# ch340_usbc.net
KiCad netlist of a schematic drawn in Altium Designer
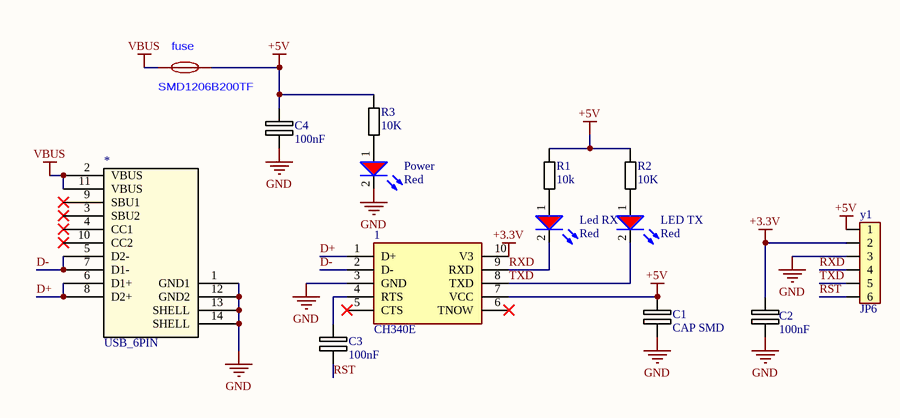
[diagram p0: ch340_usbc.SchDoc]

(export (version "E")
  (design (tool "Eeschema 10.0.6"))
  (components
    (comp (ref "*")
      (value "USB_6PIN")
      (footprint "USB-C-SMD_TYPE-C-6PIN-2MD-073")
      (libsource (lib "iot_vision") (part "USB_6PIN"))
    )
    (comp (ref "1") (value "CH340E") (footprint "ADS1115 SMD") (libsource (lib "TEST") (part "CH340E")))
    (comp (ref "C1")
      (value "CAP SMD")
      (footprint "C-0805")
      (description "Capacitor Polarised")
      (fields
        (field (name "MANUFACTURER_PART_NUMBER") "TAJC227K006RNJV")
        (field (name "MOUSER PART NUMBER") "581-TAJC227K006RNJV")
      )
      (libsource (lib "TEST") (part "CAP SMD"))
    )
    (comp (ref "C2")
      (value "100nF")
      (footprint "C-0805")
      (description "Capacitor Polarised")
      (fields
        (field (name "MANUFACTURER_PART_NUMBER") "TAJC227K006RNJV")
        (field (name "MOUSER PART NUMBER") "581-TAJC227K006RNJV")
      )
      (libsource (lib "") (part "CAP SMD_1"))
    )
    (comp (ref "C3")
      (value "100nF")
      (footprint "C-0805")
      (description "Capacitor Polarised")
      (fields
        (field (name "MANUFACTURER_PART_NUMBER") "TAJC227K006RNJV")
        (field (name "MOUSER PART NUMBER") "581-TAJC227K006RNJV")
      )
      (libsource (lib "TEST") (part "CAP SMD"))
    )
    (comp (ref "C4")
      (value "100nF")
      (footprint "C-0805")
      (description "Capacitor Polarised")
      (fields
        (field (name "MANUFACTURER_PART_NUMBER") "TAJC227K006RNJV")
        (field (name "MOUSER PART NUMBER") "581-TAJC227K006RNJV")
      )
      (libsource (lib "TEST") (part "CAP SMD"))
    )
    (comp (ref "fuse")
      (value "SMD1206B200TF")
      (footprint "F1206")
      (libsource (lib "Free Documents") (part "SMD1206B200TF"))
    )
    (comp (ref "Led RX")
      (value "Red")
      (footprint "Led 0805R")
      (description "LED Red 2mA 1.8V 0805")
      (fields (field (name "Comment") "LED-0805RVC"))
      (libsource (lib "TEST") (part "LED-0805RVC"))
    )
    (comp (ref "LED TX")
      (value "Red")
      (footprint "Led 0805R")
      (description "LED Red 2mA 1.8V 0805")
      (fields (field (name "Comment") "LED-0805RVC"))
      (libsource (lib "TEST") (part "LED-0805RVC"))
    )
    (comp (ref "Power")
      (value "LED-0805RVC")
      (footprint "Led 0805R")
      (description "LED Red 2mA 1.8V 0805")
      (fields (field (name "ALTIUM_UNNAMED_1") "Red"))
      (libsource (lib "TEST") (part "LED-0805RVC"))
    )
    (comp (ref "R1") (value "10k") (footprint "R0603") (libsource (lib "iot_vision") (part "res_0603")))
    (comp (ref "R2")
      (value "10K")
      (footprint "R0603")
      (description "Resistor")
      (libsource (lib "SamacSys") (part "Resistor"))
    )
    (comp (ref "R3")
      (value "10K")
      (footprint "R0603")
      (description "Resistor")
      (libsource (lib "SamacSys") (part "Resistor"))
    )
    (comp (ref "y1") (value "JP6") (footprint "JP6-D1T") (libsource (lib "TEST") (part "JP6")))
  )
  (nets
    (net (code "1") (name "+3.3V") (class "Default")
      (node (ref "1") (pin "10") (pinfunction "V3_10") (pintype "passive"))
      (node (ref "C2") (pin "1") (pinfunction "+_1") (pintype "passive"))
      (node (ref "y1") (pin "2") (pinfunction "2_2") (pintype "passive"))
    )
    (net (code "2") (name "+5V") (class "Default")
      (node (ref "1") (pin "7") (pinfunction "VCC_7") (pintype "passive"))
      (node (ref "C1") (pin "2") (pinfunction "-_2") (pintype "passive"))
      (node (ref "C4") (pin "2") (pinfunction "-_2") (pintype "passive"))
      (node (ref "R1") (pin "2") (pinfunction "2_2") (pintype "passive"))
      (node (ref "R2") (pin "2") (pinfunction "2_2") (pintype "passive"))
      (node (ref "R3") (pin "2") (pinfunction "2_2") (pintype "passive"))
      (node (ref "fuse") (pin "2") (pinfunction "2_2") (pintype "passive"))
      (node (ref "y1") (pin "1") (pinfunction "1_1") (pintype "passive"))
    )
    (net (code "3") (name "/D+") (class "Default")
      (node (ref "*") (pin "6") (pinfunction "D1+_6") (pintype "passive"))
      (node (ref "*") (pin "8") (pinfunction "D2+_8") (pintype "passive"))
      (node (ref "1") (pin "1") (pinfunction "D+_1") (pintype "passive"))
    )
    (net (code "4") (name "/D-") (class "Default")
      (node (ref "*") (pin "5") (pinfunction "D2-_5") (pintype "passive"))
      (node (ref "*") (pin "7") (pinfunction "D1-_7") (pintype "passive"))
      (node (ref "1") (pin "2") (pinfunction "D-_2") (pintype "passive"))
    )
    (net (code "5") (name "/RST") (class "Default")
      (node (ref "C3") (pin "1") (pinfunction "+_1") (pintype "passive"))
      (node (ref "y1") (pin "6") (pinfunction "6_6") (pintype "passive"))
    )
    (net (code "6") (name "/RXD") (class "Default")
      (node (ref "1") (pin "9") (pinfunction "RXD_9") (pintype "passive"))
      (node (ref "Led RX") (pin "2") (pinfunction "K_2") (pintype "passive"))
      (node (ref "y1") (pin "4") (pinfunction "4_4") (pintype "passive"))
    )
    (net (code "7") (name "/TXD") (class "Default")
      (node (ref "1") (pin "8") (pinfunction "TXD_8") (pintype "passive"))
      (node (ref "LED TX") (pin "2") (pinfunction "K_2") (pintype "passive"))
      (node (ref "y1") (pin "5") (pinfunction "5_5") (pintype "passive"))
    )
    (net (code "8") (name "GND") (class "Default")
      (node (ref "*") (pin "1") (pinfunction "GND1_1") (pintype "passive"))
      (node (ref "*") (pin "12") (pinfunction "GND2_12") (pintype "passive"))
      (node (ref "*") (pin "13") (pinfunction "SHELL_13") (pintype "passive"))
      (node (ref "*") (pin "14") (pinfunction "SHELL_14") (pintype "passive"))
      (node (ref "1") (pin "3") (pinfunction "GND_3") (pintype "passive"))
      (node (ref "C1") (pin "1") (pinfunction "+_1") (pintype "passive"))
      (node (ref "C2") (pin "2") (pinfunction "-_2") (pintype "passive"))
      (node (ref "C4") (pin "1") (pinfunction "+_1") (pintype "passive"))
      (node (ref "Power") (pin "2") (pinfunction "K_2") (pintype "passive"))
      (node (ref "y1") (pin "3") (pinfunction "3_3") (pintype "passive"))
    )
    (net (code "9") (name "Net-(1-RTS)") (class "Default")
      (node (ref "1") (pin "4") (pinfunction "RTS_4") (pintype "passive"))
      (node (ref "C3") (pin "2") (pinfunction "-_2") (pintype "passive"))
    )
    (net (code "10") (name "Net-(LED TX-A)") (class "Default")
      (node (ref "LED TX") (pin "1") (pinfunction "A_1") (pintype "passive"))
      (node (ref "R2") (pin "1") (pinfunction "1_1") (pintype "passive"))
    )
    (net (code "11") (name "Net-(Led RX-A)") (class "Default")
      (node (ref "Led RX") (pin "1") (pinfunction "A_1") (pintype "passive"))
      (node (ref "R1") (pin "1") (pinfunction "1_1") (pintype "passive"))
    )
    (net (code "12") (name "Net-(Power-A)") (class "Default")
      (node (ref "Power") (pin "1") (pinfunction "A_1") (pintype "passive"))
      (node (ref "R3") (pin "1") (pinfunction "1_1") (pintype "passive"))
    )
    (net (code "13") (name "VBUS") (class "Default")
      (node (ref "*") (pin "11") (pinfunction "VBUS_11") (pintype "passive"))
      (node (ref "*") (pin "2") (pinfunction "VBUS_2") (pintype "passive"))
      (node (ref "fuse") (pin "1") (pinfunction "1_1") (pintype "passive"))
    )
    (net (code "14") (name "unconnected-(*-CC1-Pad4)") (class "Default")
      (node (ref "*") (pin "4") (pinfunction "CC1_4") (pintype "passive+no_connect"))
    )
    (net (code "15") (name "unconnected-(*-CC2-Pad10)") (class "Default")
      (node (ref "*") (pin "10") (pinfunction "CC2_10") (pintype "passive+no_connect"))
    )
    (net (code "16") (name "unconnected-(*-SBU1-Pad9)") (class "Default")
      (node (ref "*") (pin "9") (pinfunction "SBU1_9") (pintype "passive+no_connect"))
    )
    (net (code "17") (name "unconnected-(*-SBU2-Pad3)") (class "Default")
      (node (ref "*") (pin "3") (pinfunction "SBU2_3") (pintype "passive+no_connect"))
    )
    (net (code "18") (name "unconnected-(1-CTS-Pad5)") (class "Default")
      (node (ref "1") (pin "5") (pinfunction "CTS_5") (pintype "passive+no_connect"))
    )
    (net (code "19") (name "unconnected-(1-TNOW-Pad6)") (class "Default")
      (node (ref "1") (pin "6") (pinfunction "TNOW_6") (pintype "passive+no_connect"))
    )
  )
)
